# stm32_ros_car.net
KiCad netlist of a schematic drawn in Altium Designer
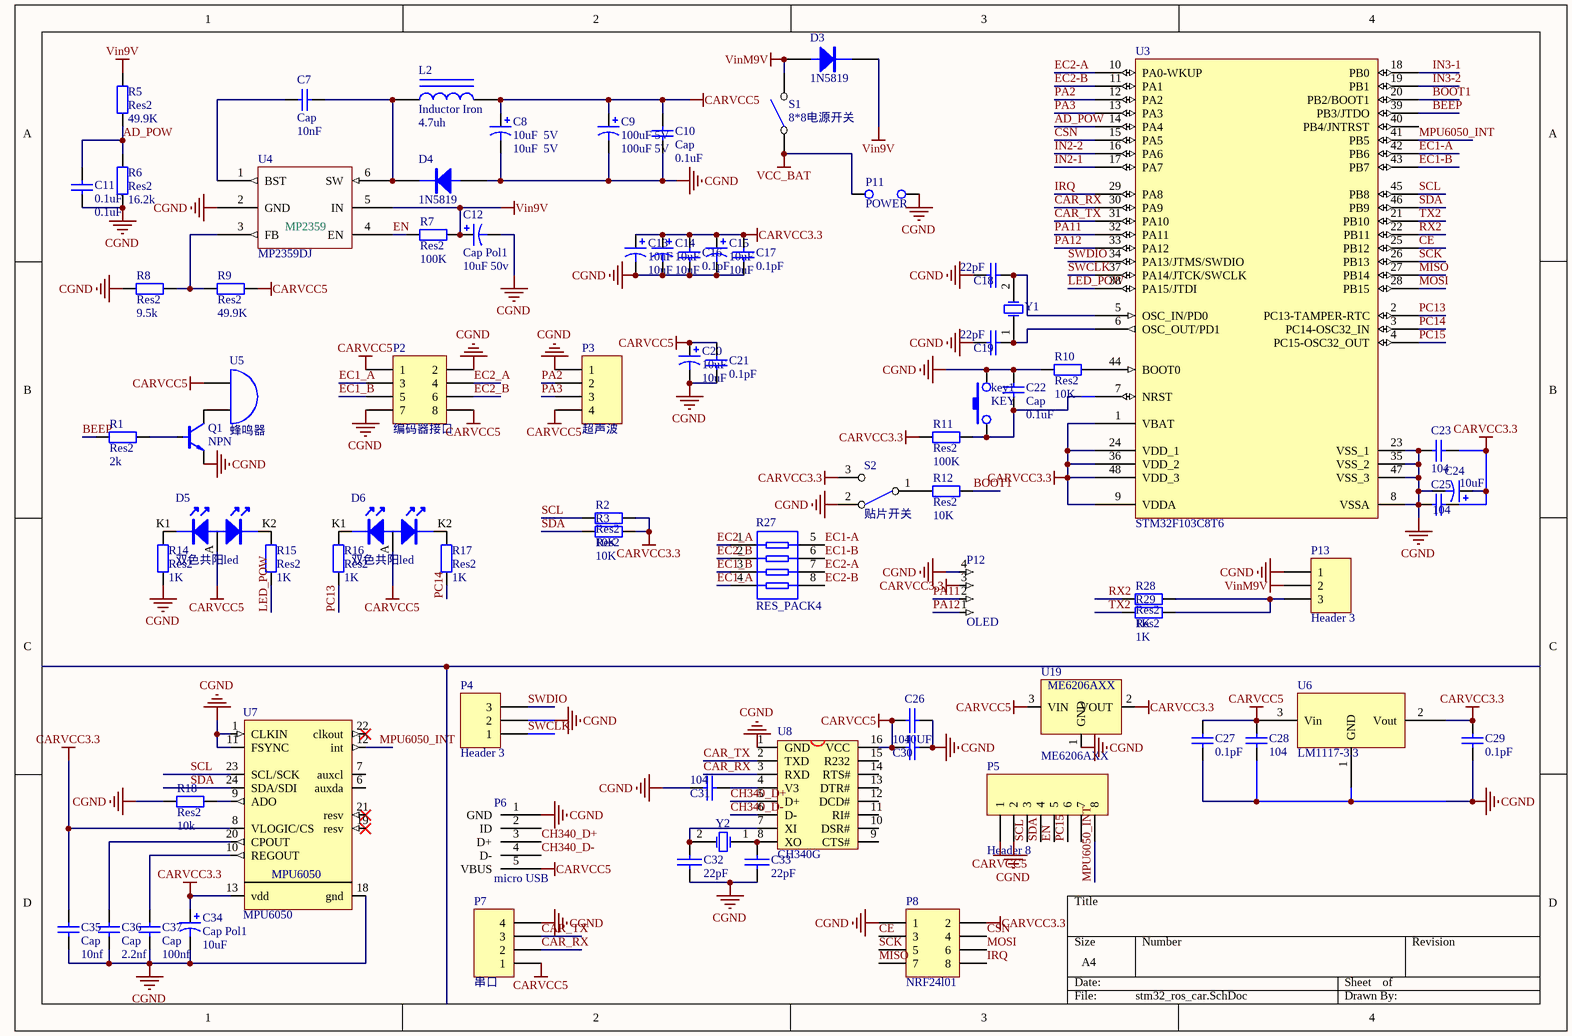
[diagram p0: stm32_ros_car.SchDoc]

(export (version "E")
  (design (tool "Eeschema 10.0.6"))
  (components
    (comp (ref "C7")
      (value "Cap")
      (footprint "LC-0603_C")
      (description "Capacitor")
      (fields (field (name "ALTIUM_VALUE") "10nF") (field (name "PUBLISHER") "Altium Limited"))
      (libsource (lib "Miscellaneous Devices") (part "Cap"))
    )
    (comp (ref "C8")
      (value "10uF  5V")
      (footprint "LC-1210_C")
      (description "Polarized Capacitor (Radial)")
      (fields (field (name "ALTIUM_VALUE") "10uF  5V") (field (name "PUBLISHER") "Altium Limited"))
      (libsource (lib "Miscellaneous Devices") (part "Cap Pol1"))
    )
    (comp (ref "C9")
      (value "100uF 5V")
      (footprint "电容HONOR_63X77")
      (description "Polarized Capacitor (Radial)")
      (fields (field (name "ALTIUM_VALUE") "100uF 5V") (field (name "PUBLISHER") "Altium Limited"))
      (libsource (lib "Miscellaneous Devices") (part "Cap Pol1"))
    )
    (comp (ref "C10")
      (value "Cap")
      (footprint "LC-0603_C")
      (description "Capacitor")
      (fields (field (name "ALTIUM_VALUE") "0.1uF") (field (name "PUBLISHER") "Altium Limited"))
      (libsource (lib "Miscellaneous Devices") (part "Cap"))
    )
    (comp (ref "C11")
      (value "0.1uF")
      (footprint "LC-0603_C")
      (description "Capacitor")
      (fields (field (name "ALTIUM_VALUE") "0.1uF") (field (name "PUBLISHER") "Altium Limited"))
      (libsource (lib "Miscellaneous Devices") (part "Cap"))
    )
    (comp (ref "C12")
      (value "Cap Pol1")
      (footprint "电容HONOR_63X54")
      (description "Polarized Capacitor (Radial)")
      (fields (field (name "ALTIUM_VALUE") "10uF 50v") (field (name "PUBLISHER") "Altium Limited"))
      (libsource (lib "Miscellaneous Devices") (part "Cap Pol1"))
    )
    (comp (ref "C13")
      (value "10uF")
      (footprint "电容HONOR_63X77")
      (description "Polarized Capacitor (Radial)")
      (fields (field (name "ALTIUM_VALUE") "10uF") (field (name "PUBLISHER") "Altium Limited"))
      (libsource (lib "Miscellaneous Devices") (part "Cap Pol1"))
    )
    (comp (ref "C14")
      (value "10uF")
      (footprint "LC-1210_C")
      (description "Polarized Capacitor (Radial)")
      (fields (field (name "ALTIUM_VALUE") "10uF") (field (name "PUBLISHER") "Altium Limited"))
      (libsource (lib "Miscellaneous Devices") (part "Cap Pol1"))
    )
    (comp (ref "C15")
      (value "10uF")
      (footprint "LC-1210_C")
      (description "Polarized Capacitor (Radial)")
      (fields (field (name "ALTIUM_VALUE") "10uF") (field (name "PUBLISHER") "Altium Limited"))
      (libsource (lib "Miscellaneous Devices") (part "Cap Pol1"))
    )
    (comp (ref "C16")
      (value "0.1pF")
      (footprint "LC-0603_C")
      (description "Capacitor")
      (fields (field (name "Comment") "Cap") (field (name "PUBLISHER") "Altium Limited"))
      (libsource (lib "Miscellaneous Devices") (part "Cap"))
    )
    (comp (ref "C17")
      (value "0.1pF")
      (footprint "LC-0603_C")
      (description "Capacitor")
      (fields (field (name "Comment") "Cap") (field (name "PUBLISHER") "Altium Limited"))
      (libsource (lib "Miscellaneous Devices") (part "Cap"))
    )
    (comp (ref "C18")
      (value "22pF")
      (footprint "LC-0603_C")
      (fields (field (name "Comment") "CAP"))
      (libsource (lib "MySchLib") (part "CAP"))
    )
    (comp (ref "C19")
      (value "22pF")
      (footprint "LC-0603_C")
      (fields (field (name "Comment") "CAP"))
      (libsource (lib "MySchLib") (part "CAP"))
    )
    (comp (ref "C20")
      (value "10uF")
      (footprint "LC-1210_C")
      (description "Polarized Capacitor (Radial)")
      (fields (field (name "ALTIUM_VALUE") "10uF") (field (name "PUBLISHER") "Altium Limited"))
      (libsource (lib "Miscellaneous Devices") (part "Cap Pol1"))
    )
    (comp (ref "C21")
      (value "0.1pF")
      (footprint "LC-0603_C")
      (description "Capacitor")
      (fields (field (name "Comment") "Cap") (field (name "PUBLISHER") "Altium Limited"))
      (libsource (lib "Miscellaneous Devices") (part "Cap"))
    )
    (comp (ref "C22")
      (value "Cap")
      (footprint "LC-0603_C")
      (description "Capacitor")
      (fields (field (name "ALTIUM_VALUE") "0.1uF") (field (name "PUBLISHER") "Altium Limited"))
      (libsource (lib "Miscellaneous Devices") (part "Cap"))
    )
    (comp (ref "C23")
      (value "104")
      (footprint "LC-0603_C")
      (description "Capacitor")
      (fields (field (name "Comment") "Cap") (field (name "PUBLISHER") "Altium Limited"))
      (libsource (lib "Miscellaneous Devices") (part "Cap"))
    )
    (comp (ref "C24")
      (value "10uF")
      (footprint "LC-1210_C")
      (description "Polarized Capacitor (Radial)")
      (fields (field (name "PUBLISHER") "Altium Limited"))
      (libsource (lib "Miscellaneous Devices") (part "Cap Pol1"))
    )
    (comp (ref "C25")
      (value "104")
      (footprint "LC-0603_C")
      (description "Capacitor")
      (fields (field (name "Comment") "Cap") (field (name "PUBLISHER") "Altium Limited"))
      (libsource (lib "Miscellaneous Devices") (part "Cap"))
    )
    (comp (ref "C26")
      (value "10UF")
      (footprint "LC-0603_C")
      (fields (field (name "Comment") "CAP"))
      (libsource (lib "MySchLib") (part "CAP"))
    )
    (comp (ref "C27")
      (value "0.1pF")
      (footprint "LC-0603_C")
      (description "Capacitor")
      (fields (field (name "Comment") "Cap") (field (name "PUBLISHER") "Altium Limited"))
      (libsource (lib "Miscellaneous Devices") (part "Cap"))
    )
    (comp (ref "C28")
      (value "104")
      (footprint "LC-Standard-FootPrints-AD-V1.00:LC-1210_C")
      (description "Capacitor")
      (fields (field (name "Comment") "Cap") (field (name "PUBLISHER") "Altium Limited"))
      (libsource (lib "Miscellaneous Devices") (part "Cap"))
    )
    (comp (ref "C29")
      (value "0.1pF")
      (footprint "LC-0603_C")
      (description "Capacitor")
      (fields (field (name "Comment") "Cap") (field (name "PUBLISHER") "Altium Limited"))
      (libsource (lib "Miscellaneous Devices") (part "Cap"))
    )
    (comp (ref "C30")
      (value "104")
      (footprint "LC-1206_C")
      (fields (field (name "Comment") "CAP"))
      (libsource (lib "MySchLib") (part "CAP"))
    )
    (comp (ref "C31")
      (value "104")
      (footprint "LC-0603_C")
      (fields (field (name "Comment") "CAP"))
      (libsource (lib "MySchLib") (part "CAP"))
    )
    (comp (ref "C32")
      (value "22pF")
      (footprint "LC-0603_C")
      (fields (field (name "Comment") "CAP"))
      (libsource (lib "MySchLib") (part "CAP"))
    )
    (comp (ref "C33")
      (value "22pF")
      (footprint "LC-0603_C")
      (fields (field (name "Comment") "CAP"))
      (libsource (lib "MySchLib") (part "CAP"))
    )
    (comp (ref "C34")
      (value "Cap Pol1")
      (footprint "LC-1210_C")
      (description "Polarized Capacitor (Radial)")
      (fields (field (name "ALTIUM_VALUE") "10uF") (field (name "PUBLISHER") "Altium Limited"))
      (libsource (lib "Miscellaneous Devices") (part "Cap Pol1"))
    )
    (comp (ref "C35")
      (value "Cap")
      (footprint "LC-0603_C")
      (description "Capacitor")
      (fields (field (name "ALTIUM_VALUE") "10nf") (field (name "PUBLISHER") "Altium Limited"))
      (libsource (lib "Miscellaneous Devices") (part "Cap"))
    )
    (comp (ref "C36")
      (value "Cap")
      (footprint "LC-0603_C")
      (description "Capacitor")
      (fields (field (name "ALTIUM_VALUE") "2.2nf") (field (name "PUBLISHER") "Altium Limited"))
      (libsource (lib "Miscellaneous Devices") (part "Cap"))
    )
    (comp (ref "C37")
      (value "Cap")
      (footprint "LC-0603_C")
      (description "Capacitor")
      (fields (field (name "ALTIUM_VALUE") "100nf") (field (name "PUBLISHER") "Altium Limited"))
      (libsource (lib "Miscellaneous Devices") (part "Cap"))
    )
    (comp (ref "D3") (value "1N5819") (footprint "SMA") (libsource (lib "ARAMYLIB") (part "1N4001")))
    (comp (ref "D4") (value "1N5819") (footprint "SMA") (libsource (lib "ARAMYLIB") (part "1N4001")))
    (comp (ref "D5") (value "双色共阳led") (footprint "共阳双色LED") (libsource (lib "ROS_CAR_LIB") (part "双色共阳led")))
    (comp (ref "D6") (value "双色共阳led") (footprint "共阳双色LED") (libsource (lib "ROS_CAR_LIB") (part "双色共阳led")))
    (comp (ref "key1") (value "KEY") (footprint "SMD轻触按键") (libsource (lib "ROS_CAR_LIB") (part "KEY")))
    (comp (ref "L2")
      (value "Inductor Iron")
      (footprint "电感GDCD4532")
      (description "Magnetic-Core Inductor")
      (fields (field (name "ALTIUM_VALUE") "4.7uh") (field (name "PUBLISHER") "Altium Limited"))
      (libsource (lib "Miscellaneous Devices") (part "Inductor Iron"))
    )
    (comp (ref "P2")
      (value "编码器接口")
      (footprint "HDR2X4")
      (description "Header, 4-Pin, Dual row")
      (fields (field (name "PUBLISHER") "Altium Limited"))
      (libsource (lib "Miscellaneous Connectors") (part "Header 4X2"))
    )
    (comp (ref "P3")
      (value "超声波")
      (footprint "HDR1X4")
      (description "Header, 4-Pin")
      (fields (field (name "PUBLISHER") "Altium Limited"))
      (libsource (lib "Miscellaneous Connectors") (part "Header 4"))
    )
    (comp (ref "P4")
      (value "Header 3")
      (footprint "HDR1X3")
      (description "Header, 3-Pin")
      (fields (field (name "PUBLISHER") "Altium Limited"))
      (libsource (lib "Miscellaneous Connectors") (part "Header 3"))
    )
    (comp (ref "P5")
      (value "Header 8")
      (footprint "HDR1X8")
      (description "Header, 8-Pin")
      (fields (field (name "PUBLISHER") "Altium Limited"))
      (libsource (lib "Miscellaneous Connectors") (part "Header 8"))
    )
    (comp (ref "P6")
      (value "micro USB")
      (footprint "micro 5P沉板式0.8四脚全插无导位有孔")
      (libsource (lib "ROS_CAR_LIB") (part "micro 5P"))
    )
    (comp (ref "P7")
      (value "串口")
      (footprint "HDR1X4")
      (description "Header, 4-Pin")
      (fields (field (name "PUBLISHER") "Altium Limited"))
      (libsource (lib "") (part "Header 4_1"))
    )
    (comp (ref "P8")
      (value "NRF24l01")
      (footprint "HDR2X4")
      (description "Header, 4-Pin, Dual row")
      (fields (field (name "PUBLISHER") "Altium Limited"))
      (libsource (lib "Miscellaneous Connectors") (part "Header 4X2"))
    )
    (comp (ref "P11") (value "POWER") (footprint "电源") (libsource (lib "ROS_CAR_LIB") (part "POWER")))
    (comp (ref "P12")
      (value "OLED")
      (footprint "1.0MM 翻盖 下接 FPC连接器 4P")
      (libsource (lib "ros_car_lib") (part "FPC 4P 1MM"))
    )
    (comp (ref "P13")
      (value "Header 3")
      (footprint "AMP 3针连接件")
      (description "Header, 3-Pin")
      (fields (field (name "PUBLISHER") "Altium Limited"))
      (libsource (lib "") (part "Header 3_1"))
    )
    (comp (ref "Q1") (value "NPN") (footprint "LC-SOT-23") (libsource (lib "ARAMYLIB") (part "NPN")))
    (comp (ref "R1")
      (value "Res2")
      (footprint "LC-0603_R")
      (description "Resistor")
      (fields (field (name "ALTIUM_VALUE") "2k") (field (name "PUBLISHER") "Altium Limited"))
      (libsource (lib "") (part "Res2_2"))
    )
    (comp (ref "R2")
      (value "Res2")
      (footprint "LC-0603_R")
      (description "Resistor")
      (fields (field (name "ALTIUM_VALUE") "10K") (field (name "PUBLISHER") "Altium Limited"))
      (libsource (lib "") (part "Res2_2"))
    )
    (comp (ref "R3")
      (value "Res2")
      (footprint "LC-0603_R")
      (description "Resistor")
      (fields (field (name "ALTIUM_VALUE") "10K") (field (name "PUBLISHER") "Altium Limited"))
      (libsource (lib "") (part "Res2_2"))
    )
    (comp (ref "R5")
      (value "Res2")
      (footprint "LC-0603_R")
      (description "Resistor")
      (fields (field (name "ALTIUM_VALUE") "49.9K") (field (name "PUBLISHER") "Altium Limited"))
      (libsource (lib "") (part "Res2_3"))
    )
    (comp (ref "R6")
      (value "Res2")
      (footprint "LC-0603_R")
      (description "Resistor")
      (fields (field (name "ALTIUM_VALUE") "16.2k") (field (name "PUBLISHER") "Altium Limited"))
      (libsource (lib "") (part "Res2_3"))
    )
    (comp (ref "R7")
      (value "Res2")
      (footprint "LC-0603_R")
      (description "Resistor")
      (fields (field (name "ALTIUM_VALUE") "100K") (field (name "PUBLISHER") "Altium Limited"))
      (libsource (lib "Miscellaneous Devices") (part "Res2"))
    )
    (comp (ref "R8")
      (value "Res2")
      (footprint "LC-0603_R")
      (description "Resistor")
      (fields (field (name "ALTIUM_VALUE") "9.5k") (field (name "PUBLISHER") "Altium Limited"))
      (libsource (lib "") (part "Res2_2"))
    )
    (comp (ref "R9")
      (value "Res2")
      (footprint "LC-0603_R")
      (description "Resistor")
      (fields (field (name "ALTIUM_VALUE") "49.9K") (field (name "PUBLISHER") "Altium Limited"))
      (libsource (lib "") (part "Res2_2"))
    )
    (comp (ref "R10")
      (value "Res2")
      (footprint "LC-0603_R")
      (description "Resistor")
      (fields (field (name "ALTIUM_VALUE") "10K") (field (name "PUBLISHER") "Altium Limited"))
      (libsource (lib "Miscellaneous Devices") (part "Res2"))
    )
    (comp (ref "R11")
      (value "Res2")
      (footprint "LC-0603_R")
      (description "Resistor")
      (fields (field (name "ALTIUM_VALUE") "100K") (field (name "PUBLISHER") "Altium Limited"))
      (libsource (lib "Miscellaneous Devices") (part "Res2"))
    )
    (comp (ref "R12")
      (value "Res2")
      (footprint "LC-0603_R")
      (description "Resistor")
      (fields (field (name "ALTIUM_VALUE") "10K") (field (name "PUBLISHER") "Altium Limited"))
      (libsource (lib "") (part "Res2_2"))
    )
    (comp (ref "R14")
      (value "Res2")
      (footprint "LC-0603_R")
      (description "Resistor")
      (fields (field (name "ALTIUM_VALUE") "1K") (field (name "PUBLISHER") "Altium Limited"))
      (libsource (lib "") (part "Res2_1"))
    )
    (comp (ref "R15")
      (value "Res2")
      (footprint "LC-0603_R")
      (description "Resistor")
      (fields (field (name "ALTIUM_VALUE") "1K") (field (name "PUBLISHER") "Altium Limited"))
      (libsource (lib "") (part "Res2_1"))
    )
    (comp (ref "R16")
      (value "Res2")
      (footprint "LC-0603_R")
      (description "Resistor")
      (fields (field (name "ALTIUM_VALUE") "1K") (field (name "PUBLISHER") "Altium Limited"))
      (libsource (lib "") (part "Res2_1"))
    )
    (comp (ref "R17")
      (value "Res2")
      (footprint "LC-0603_R")
      (description "Resistor")
      (fields (field (name "ALTIUM_VALUE") "1K") (field (name "PUBLISHER") "Altium Limited"))
      (libsource (lib "") (part "Res2_1"))
    )
    (comp (ref "R18")
      (value "Res2")
      (footprint "LC-0603_R")
      (description "Resistor")
      (fields (field (name "ALTIUM_VALUE") "10k") (field (name "PUBLISHER") "Altium Limited"))
      (libsource (lib "") (part "Res2_2"))
    )
    (comp (ref "R27") (value "RES_PACK4") (footprint "RES4") (libsource (lib "ARAMYLIB") (part "RES_PACK4")))
    (comp (ref "R28")
      (value "Res2")
      (footprint "LC-0603_R")
      (description "Resistor")
      (fields (field (name "ALTIUM_VALUE") "1K") (field (name "PUBLISHER") "Altium Limited"))
      (libsource (lib "Miscellaneous Devices") (part "Res2"))
    )
    (comp (ref "R29")
      (value "Res2")
      (footprint "LC-0603_R")
      (description "Resistor")
      (fields (field (name "ALTIUM_VALUE") "1K") (field (name "PUBLISHER") "Altium Limited"))
      (libsource (lib "Miscellaneous Devices") (part "Res2"))
    )
    (comp (ref "S1") (value "8*8电源开关") (footprint "8*8自锁开关") (libsource (lib "ROS_CAR_LIB") (part "8*8电源开关")))
    (comp (ref "S2") (value "贴片开关") (footprint "KEY") (libsource (lib "aramy_四轴") (part "贴片开关")))
    (comp (ref "U3")
      (value "STM32F103C8T6")
      (footprint "LQFP48_L")
      (description "STM32 ARM-based 32-bit MCU with 64 Kbytes Flash, 48-pin LQFP, Industrial Temperature")
      (fields (field (name "PUBLISHER") "Altium Limited"))
      (libsource (lib "ST Microcontroller 32-Bit STM32") (part "STM32F103C8T6"))
    )
    (comp (ref "U4")
      (value "MP2359DJ")
      (footprint "LC-SOT-23-6")
      (libsource (lib "ARAMYLIB") (part "MP2359DJ"))
    )
    (comp (ref "U5")
      (value "蜂鸣器")
      (footprint "BELL")
      (description "Bell")
      (libsource (lib "ARAMYLIB") (part "蜂鸣器"))
    )
    (comp (ref "U6")
      (value "LM1117-3.3")
      (footprint "SOT223")
      (libsource (lib "MySchLib") (part "LM1117-3.3"))
    )
    (comp (ref "U7") (value "MPU6050") (footprint "QFN24") (libsource (lib "aramy_四轴") (part "MPU6050")))
    (comp (ref "U8")
      (value "CH340G")
      (footprint "SOP16M")
      (description "USB2UART")
      (libsource (lib "EliteSTM32封装库") (part "CH340G"))
    )
    (comp (ref "U19")
      (value "ME6206AXX")
      (footprint "LC-SOT-89")
      (libsource (lib "ARAMY_四轴") (part "ME6206AXX"))
    )
    (comp (ref "Y1")
      (value "12MHz")
      (footprint "49SMD")
      (description "Crystal Oscillator")
      (fields (field (name "PUBLISHER") "Altium Limited"))
      (libsource (lib "ALIENTEK_底板封装库") (part "XTAL"))
    )
    (comp (ref "Y2")
      (value "12MHz")
      (footprint "49SMD")
      (description "Crystal Oscillator")
      (fields (field (name "PUBLISHER") "Altium Limited"))
      (libsource (lib "ALIENTEK_底板封装库") (part "XTAL"))
    )
  )
  (nets
    (net (code "1") (name "/AD_POW") (class "Default")
      (node (ref "C11") (pin "1") (pinfunction "1_1") (pintype "passive"))
      (node (ref "R5") (pin "2") (pinfunction "2_2") (pintype "passive"))
      (node (ref "R6") (pin "1") (pinfunction "1_1") (pintype "passive"))
      (node (ref "U3") (pin "14") (pinfunction "PA4_14") (pintype "bidirectional"))
    )
    (net (code "2") (name "/BEEP") (class "Default")
      (node (ref "R1") (pin "2") (pinfunction "2_2") (pintype "passive"))
      (node (ref "U3") (pin "39") (pinfunction "PB3/JTDO_39") (pintype "bidirectional"))
    )
    (net (code "3") (name "/BOOT1") (class "Default")
      (node (ref "R12") (pin "1") (pinfunction "1_1") (pintype "passive"))
      (node (ref "U3") (pin "20") (pinfunction "PB2/BOOT1_20") (pintype "bidirectional"))
    )
    (net (code "4") (name "/CAR_RX") (class "Default")
      (node (ref "P7") (pin "2") (pinfunction "2_2") (pintype "passive"))
      (node (ref "U3") (pin "30") (pinfunction "PA9_30") (pintype "bidirectional"))
      (node (ref "U8") (pin "3") (pinfunction "RXD_3") (pintype "passive"))
    )
    (net (code "5") (name "/CAR_TX") (class "Default")
      (node (ref "P7") (pin "3") (pinfunction "3_3") (pintype "passive"))
      (node (ref "U3") (pin "31") (pinfunction "PA10_31") (pintype "bidirectional"))
      (node (ref "U8") (pin "2") (pinfunction "TXD_2") (pintype "passive"))
    )
    (net (code "6") (name "/CE") (class "Default")
      (node (ref "P8") (pin "3") (pinfunction "3_3") (pintype "passive"))
      (node (ref "U3") (pin "25") (pinfunction "PB12_25") (pintype "bidirectional"))
    )
    (net (code "7") (name "/CH340_D+") (class "Default")
      (node (ref "P6") (pin "3") (pinfunction "D+_3") (pintype "passive"))
      (node (ref "U8") (pin "5") (pinfunction "D+_5") (pintype "passive"))
    )
    (net (code "8") (name "/CH340_D-") (class "Default")
      (node (ref "P6") (pin "4") (pinfunction "D-_4") (pintype "passive"))
      (node (ref "U8") (pin "6") (pinfunction "D-_6") (pintype "passive"))
    )
    (net (code "9") (name "/CSN") (class "Default")
      (node (ref "P8") (pin "4") (pinfunction "4_4") (pintype "passive"))
      (node (ref "U3") (pin "15") (pinfunction "PA5_15") (pintype "bidirectional"))
    )
    (net (code "10") (name "/EC1-A") (class "Default")
      (node (ref "R27") (pin "5") (pinfunction "5_5") (pintype "passive"))
      (node (ref "U3") (pin "42") (pinfunction "PB6_42") (pintype "bidirectional"))
    )
    (net (code "11") (name "/EC1-B") (class "Default")
      (node (ref "R27") (pin "6") (pinfunction "6_6") (pintype "passive"))
      (node (ref "U3") (pin "43") (pinfunction "PB7_43") (pintype "bidirectional"))
    )
    (net (code "12") (name "/EC1_A") (class "Default")
      (node (ref "P2") (pin "3") (pinfunction "3_3") (pintype "passive"))
      (node (ref "R27") (pin "4") (pinfunction "4_4") (pintype "passive"))
    )
    (net (code "13") (name "/EC1_B") (class "Default")
      (node (ref "P2") (pin "5") (pinfunction "5_5") (pintype "passive"))
      (node (ref "R27") (pin "3") (pinfunction "3_3") (pintype "passive"))
    )
    (net (code "14") (name "/EC2-A") (class "Default")
      (node (ref "R27") (pin "7") (pinfunction "7_7") (pintype "passive"))
      (node (ref "U3") (pin "10") (pinfunction "PA0-WKUP_10") (pintype "bidirectional"))
    )
    (net (code "15") (name "/EC2-B") (class "Default")
      (node (ref "R27") (pin "8") (pinfunction "8_8") (pintype "passive"))
      (node (ref "U3") (pin "11") (pinfunction "PA1_11") (pintype "bidirectional"))
    )
    (net (code "16") (name "/EC2_A") (class "Default")
      (node (ref "P2") (pin "4") (pinfunction "4_4") (pintype "passive"))
      (node (ref "R27") (pin "1") (pinfunction "1_1") (pintype "passive"))
    )
    (net (code "17") (name "/EC2_B") (class "Default")
      (node (ref "P2") (pin "6") (pinfunction "6_6") (pintype "passive"))
      (node (ref "R27") (pin "2") (pinfunction "2_2") (pintype "passive"))
    )
    (net (code "18") (name "/EN") (class "Default")
      (node (ref "P5") (pin "5") (pinfunction "5_5") (pintype "passive"))
      (node (ref "R7") (pin "1") (pinfunction "1_1") (pintype "passive"))
      (node (ref "U4") (pin "4") (pinfunction "EN_4") (pintype "power_in"))
    )
    (net (code "19") (name "/IN2-1") (class "Default")
      (node (ref "U3") (pin "17") (pinfunction "PA7_17") (pintype "bidirectional"))
    )
    (net (code "20") (name "/IN2-2") (class "Default")
      (node (ref "U3") (pin "16") (pinfunction "PA6_16") (pintype "bidirectional"))
    )
    (net (code "21") (name "/IN3-1") (class "Default")
      (node (ref "U3") (pin "18") (pinfunction "PB0_18") (pintype "bidirectional"))
    )
    (net (code "22") (name "/IN3-2") (class "Default")
      (node (ref "U3") (pin "19") (pinfunction "PB1_19") (pintype "bidirectional"))
    )
    (net (code "23") (name "/IRQ") (class "Default")
      (node (ref "P8") (pin "8") (pinfunction "8_8") (pintype "passive"))
      (node (ref "U3") (pin "29") (pinfunction "PA8_29") (pintype "bidirectional"))
    )
    (net (code "24") (name "/LED_POW") (class "Default")
      (node (ref "R15") (pin "1") (pinfunction "1_1") (pintype "passive"))
      (node (ref "U3") (pin "38") (pinfunction "PA15/JTDI_38") (pintype "bidirectional"))
    )
    (net (code "25") (name "/MISO") (class "Default")
      (node (ref "P8") (pin "7") (pinfunction "7_7") (pintype "passive"))
      (node (ref "U3") (pin "27") (pinfunction "PB14_27") (pintype "bidirectional"))
    )
    (net (code "26") (name "/MOSI") (class "Default")
      (node (ref "P8") (pin "6") (pinfunction "6_6") (pintype "passive"))
      (node (ref "U3") (pin "28") (pinfunction "PB15_28") (pintype "bidirectional"))
    )
    (net (code "27") (name "/MPU6050_INT") (class "Default")
      (node (ref "P5") (pin "8") (pinfunction "8_8") (pintype "passive"))
      (node (ref "U3") (pin "41") (pinfunction "PB5_41") (pintype "bidirectional"))
      (node (ref "U7") (pin "12") (pinfunction "int_12") (pintype "output"))
    )
    (net (code "28") (name "/PA2") (class "Default")
      (node (ref "P3") (pin "2") (pinfunction "2_2") (pintype "passive"))
      (node (ref "U3") (pin "12") (pinfunction "PA2_12") (pintype "bidirectional"))
    )
    (net (code "29") (name "/PA3") (class "Default")
      (node (ref "P3") (pin "3") (pinfunction "3_3") (pintype "passive"))
      (node (ref "U3") (pin "13") (pinfunction "PA3_13") (pintype "bidirectional"))
    )
    (net (code "30") (name "/PA11") (class "Default")
      (node (ref "P12") (pin "2") (pinfunction "2_2") (pintype "input"))
      (node (ref "U3") (pin "32") (pinfunction "PA11_32") (pintype "bidirectional"))
    )
    (net (code "31") (name "/PA12") (class "Default")
      (node (ref "P12") (pin "1") (pinfunction "1_1") (pintype "input"))
      (node (ref "U3") (pin "33") (pinfunction "PA12_33") (pintype "bidirectional"))
    )
    (net (code "32") (name "/PC13") (class "Default")
      (node (ref "R16") (pin "1") (pinfunction "1_1") (pintype "passive"))
      (node (ref "U3") (pin "2") (pinfunction "PC13-TAMPER-RTC_2") (pintype "bidirectional"))
    )
    (net (code "33") (name "/PC14") (class "Default")
      (node (ref "R17") (pin "1") (pinfunction "1_1") (pintype "passive"))
      (node (ref "U3") (pin "3") (pinfunction "PC14-OSC32_IN_3") (pintype "bidirectional"))
    )
    (net (code "34") (name "/PC15") (class "Default")
      (node (ref "P5") (pin "6") (pinfunction "6_6") (pintype "passive"))
      (node (ref "U3") (pin "4") (pinfunction "PC15-OSC32_OUT_4") (pintype "bidirectional"))
    )
    (net (code "35") (name "/RX2") (class "Default")
      (node (ref "R28") (pin "1") (pinfunction "1_1") (pintype "passive"))
      (node (ref "U3") (pin "22") (pinfunction "PB11_22") (pintype "bidirectional"))
    )
    (net (code "36") (name "/SCK") (class "Default")
      (node (ref "P8") (pin "5") (pinfunction "5_5") (pintype "passive"))
      (node (ref "U3") (pin "26") (pinfunction "PB13_26") (pintype "bidirectional"))
    )
    (net (code "37") (name "/SCL") (class "Default")
      (node (ref "P5") (pin "3") (pinfunction "3_3") (pintype "passive"))
      (node (ref "R2") (pin "2") (pinfunction "2_2") (pintype "passive"))
      (node (ref "U3") (pin "45") (pinfunction "PB8_45") (pintype "bidirectional"))
      (node (ref "U7") (pin "23") (pinfunction "SCL/SCK_23") (pintype "bidirectional"))
    )
    (net (code "38") (name "/SDA") (class "Default")
      (node (ref "P5") (pin "4") (pinfunction "4_4") (pintype "passive"))
      (node (ref "R3") (pin "2") (pinfunction "2_2") (pintype "passive"))
      (node (ref "U3") (pin "46") (pinfunction "PB9_46") (pintype "bidirectional"))
      (node (ref "U7") (pin "24") (pinfunction "SDA/SDI_24") (pintype "bidirectional"))
    )
    (net (code "39") (name "/SWCLK") (class "Default")
      (node (ref "P4") (pin "1") (pinfunction "1_1") (pintype "passive"))
      (node (ref "U3") (pin "37") (pinfunction "PA14/JTCK/SWCLK_37") (pintype "bidirectional"))
    )
    (net (code "40") (name "/SWDIO") (class "Default")
      (node (ref "P4") (pin "3") (pinfunction "3_3") (pintype "passive"))
      (node (ref "U3") (pin "34") (pinfunction "PA13/JTMS/SWDIO_34") (pintype "bidirectional"))
    )
    (net (code "41") (name "/TX2") (class "Default")
      (node (ref "R29") (pin "1") (pinfunction "1_1") (pintype "passive"))
      (node (ref "U3") (pin "21") (pinfunction "PB10_21") (pintype "bidirectional"))
    )
    (net (code "42") (name "CARVCC3.3") (class "Default")
      (node (ref "C13") (pin "1") (pinfunction "1_1") (pintype "passive"))
      (node (ref "C14") (pin "1") (pinfunction "1_1") (pintype "passive"))
      (node (ref "C15") (pin "1") (pinfunction "1_1") (pintype "passive"))
      (node (ref "C16") (pin "1") (pinfunction "1_1") (pintype "passive"))
      (node (ref "C17") (pin "1") (pinfunction "1_1") (pintype "passive"))
      (node (ref "C23") (pin "1") (pinfunction "1_1") (pintype "passive"))
      (node (ref "C24") (pin "1") (pinfunction "1_1") (pintype "passive"))
      (node (ref "C25") (pin "1") (pinfunction "1_1") (pintype "passive"))
      (node (ref "C29") (pin "1") (pinfunction "1_1") (pintype "passive"))
      (node (ref "C34") (pin "1") (pinfunction "1_1") (pintype "passive"))
      (node (ref "C35") (pin "2") (pinfunction "2_2") (pintype "passive"))
      (node (ref "P12") (pin "3") (pinfunction "3_3") (pintype "input"))
      (node (ref "P8") (pin "2") (pinfunction "2_2") (pintype "passive"))
      (node (ref "R11") (pin "1") (pinfunction "1_1") (pintype "passive"))
      (node (ref "R2") (pin "1") (pinfunction "1_1") (pintype "passive"))
      (node (ref "R3") (pin "1") (pinfunction "1_1") (pintype "passive"))
      (node (ref "S2") (pin "3") (pinfunction "NO1_3") (pintype "passive"))
      (node (ref "U19") (pin "2") (pinfunction "VOUT_2") (pintype "passive"))
      (node (ref "U3") (pin "1") (pinfunction "VBAT_1") (pintype "power_in"))
      (node (ref "U3") (pin "24") (pinfunction "VDD_1_24") (pintype "power_in"))
      (node (ref "U3") (pin "36") (pinfunction "VDD_2_36") (pintype "power_in"))
      (node (ref "U3") (pin "48") (pinfunction "VDD_3_48") (pintype "power_in"))
      (node (ref "U3") (pin "9") (pinfunction "VDDA_9") (pintype "power_in"))
      (node (ref "U6") (pin "2") (pinfunction "Vout_2") (pintype "passive"))
      (node (ref "U7") (pin "13") (pinfunction "vdd_13") (pintype "power_in"))
      (node (ref "U7") (pin "8") (pinfunction "VLOGIC/CS_8") (pintype "bidirectional"))
    )
    (net (code "43") (name "CARVCC5") (class "Default")
      (node (ref "C10") (pin "2") (pinfunction "2_2") (pintype "passive"))
      (node (ref "C20") (pin "1") (pinfunction "1_1") (pintype "passive"))
      (node (ref "C21") (pin "1") (pinfunction "1_1") (pintype "passive"))
      (node (ref "C26") (pin "2") (pinfunction "2_2") (pintype "passive"))
      (node (ref "C27") (pin "1") (pinfunction "1_1") (pintype "passive"))
      (node (ref "C28") (pin "2") (pinfunction "2_2") (pintype "passive"))
      (node (ref "C30") (pin "1") (pinfunction "1_1") (pintype "passive"))
      (node (ref "C8") (pin "1") (pinfunction "1_1") (pintype "passive"))
      (node (ref "C9") (pin "1") (pinfunction "1_1") (pintype "passive"))
      (node (ref "D5") (pin "A") (pinfunction "2_A") (pintype "passive"))
      (node (ref "D6") (pin "A") (pinfunction "2_A") (pintype "passive"))
      (node (ref "L2") (pin "2") (pinfunction "2_2") (pintype "passive"))
      (node (ref "P2") (pin "1") (pinfunction "1_1") (pintype "passive"))
      (node (ref "P2") (pin "8") (pinfunction "8_8") (pintype "passive"))
      (node (ref "P3") (pin "4") (pinfunction "4_4") (pintype "passive"))
      (node (ref "P5") (pin "1") (pinfunction "1_1") (pintype "passive"))
      (node (ref "P6") (pin "5") (pinfunction "VBUS_5") (pintype "passive"))
      (node (ref "P7") (pin "1") (pinfunction "1_1") (pintype "passive"))
      (node (ref "R9") (pin "1") (pinfunction "1_1") (pintype "passive"))
      (node (ref "U19") (pin "3") (pinfunction "VIN_3") (pintype "power_in"))
      (node (ref "U5") (pin "1") (pinfunction "A_1") (pintype "passive"))
      (node (ref "U6") (pin "3") (pinfunction "Vin_3") (pintype "passive"))
      (node (ref "U8") (pin "16") (pinfunction "VCC_16") (pintype "passive"))
    )
    (net (code "44") (name "CGND") (class "Default")
      (node (ref "C10") (pin "1") (pinfunction "1_1") (pintype "passive"))
      (node (ref "C11") (pin "2") (pinfunction "2_2") (pintype "passive"))
      (node (ref "C12") (pin "2") (pinfunction "2_2") (pintype "passive"))
      (node (ref "C13") (pin "2") (pinfunction "2_2") (pintype "passive"))
      (node (ref "C14") (pin "2") (pinfunction "2_2") (pintype "passive"))
      (node (ref "C15") (pin "2") (pinfunction "2_2") (pintype "passive"))
      (node (ref "C16") (pin "2") (pinfunction "2_2") (pintype "passive"))
      (node (ref "C17") (pin "2") (pinfunction "2_2") (pintype "passive"))
      (node (ref "C18") (pin "1") (pinfunction "1_1") (pintype "passive"))
      (node (ref "C19") (pin "1") (pinfunction "1_1") (pintype "passive"))
      (node (ref "C20") (pin "2") (pinfunction "2_2") (pintype "passive"))
      (node (ref "C21") (pin "2") (pinfunction "2_2") (pintype "passive"))
      (node (ref "C22") (pin "2") (pinfunction "2_2") (pintype "passive"))
      (node (ref "C23") (pin "2") (pinfunction "2_2") (pintype "passive"))
      (node (ref "C24") (pin "2") (pinfunction "2_2") (pintype "passive"))
      (node (ref "C25") (pin "2") (pinfunction "2_2") (pintype "passive"))
      (node (ref "C26") (pin "1") (pinfunction "1_1") (pintype "passive"))
      (node (ref "C27") (pin "2") (pinfunction "2_2") (pintype "passive"))
      (node (ref "C28") (pin "1") (pinfunction "1_1") (pintype "passive"))
      (node (ref "C29") (pin "2") (pinfunction "2_2") (pintype "passive"))
      (node (ref "C30") (pin "2") (pinfunction "2_2") (pintype "passive"))
      (node (ref "C31") (pin "1") (pinfunction "1_1") (pintype "passive"))
      (node (ref "C32") (pin "1") (pinfunction "1_1") (pintype "passive"))
      (node (ref "C33") (pin "1") (pinfunction "1_1") (pintype "passive"))
      (node (ref "C34") (pin "2") (pinfunction "2_2") (pintype "passive"))
      (node (ref "C35") (pin "1") (pinfunction "1_1") (pintype "passive"))
      (node (ref "C36") (pin "1") (pinfunction "1_1") (pintype "passive"))
      (node (ref "C37") (pin "1") (pinfunction "1_1") (pintype "passive"))
      (node (ref "C8") (pin "2") (pinfunction "2_2") (pintype "passive"))
      (node (ref "C9") (pin "2") (pinfunction "2_2") (pintype "passive"))
      (node (ref "D4") (pin "A") (pinfunction "1_A") (pintype "passive"))
      (node (ref "P11") (pin "2") (pinfunction "2_2") (pintype "passive"))
      (node (ref "P12") (pin "4") (pinfunction "4_4") (pintype "input"))
      (node (ref "P13") (pin "1") (pinfunction "1_1") (pintype "passive"))
      (node (ref "P2") (pin "2") (pinfunction "2_2") (pintype "passive"))
      (node (ref "P2") (pin "7") (pinfunction "7_7") (pintype "passive"))
      (node (ref "P3") (pin "1") (pinfunction "1_1") (pintype "passive"))
      (node (ref "P4") (pin "2") (pinfunction "2_2") (pintype "passive"))
      (node (ref "P5") (pin "2") (pinfunction "2_2") (pintype "passive"))
      (node (ref "P6") (pin "1") (pinfunction "GND_1") (pintype "power_in"))
      (node (ref "P7") (pin "4") (pinfunction "4_4") (pintype "passive"))
      (node (ref "P8") (pin "1") (pinfunction "1_1") (pintype "passive"))
      (node (ref "Q1") (pin "E") (pinfunction "e_E") (pintype "passive"))
      (node (ref "R10") (pin "1") (pinfunction "1_1") (pintype "passive"))
      (node (ref "R14") (pin "1") (pinfunction "1_1") (pintype "passive"))
      (node (ref "R18") (pin "2") (pinfunction "2_2") (pintype "passive"))
      (node (ref "R6") (pin "2") (pinfunction "2_2") (pintype "passive"))
      (node (ref "R8") (pin "2") (pinfunction "2_2") (pintype "passive"))
      (node (ref "S2") (pin "2") (pinfunction "NC1_2") (pintype "passive"))
      (node (ref "U19") (pin "1") (pinfunction "GND_1") (pintype "power_in"))
      (node (ref "U3") (pin "23") (pinfunction "VSS_1_23") (pintype "power_in"))
      (node (ref "U3") (pin "35") (pinfunction "VSS_2_35") (pintype "power_in"))
      (node (ref "U3") (pin "47") (pinfunction "VSS_3_47") (pintype "power_in"))
      (node (ref "U3") (pin "8") (pinfunction "VSSA_8") (pintype "power_in"))
      (node (ref "U4") (pin "2") (pinfunction "GND_2") (pintype "power_in"))
      (node (ref "U6") (pin "1") (pinfunction "GND_1") (pintype "passive"))
      (node (ref "U7") (pin "1") (pinfunction "CLKIN_1") (pintype "input"))
      (node (ref "U7") (pin "11") (pinfunction "FSYNC_11") (pintype "bidirectional"))
      (node (ref "U7") (pin "18") (pinfunction "gnd_18") (pintype "power_in"))
      (node (ref "U8") (pin "1") (pinfunction "GND_1") (pintype "passive"))
      (node (ref "key1") (pin "2") (pinfunction "2_2") (pintype "passive"))
    )
    (net (code "45") (name "Net-(D4-2)") (class "Default")
      (node (ref "C7") (pin "2") (pinfunction "2_2") (pintype "passive"))
      (node (ref "D4") (pin "K") (pinfunction "2_K") (pintype "passive"))
      (node (ref "L2") (pin "1") (pinfunction "1_1") (pintype "passive"))
      (node (ref "U4") (pin "6") (pinfunction "SW_6") (pintype "input"))
    )
    (net (code "46") (name "Net-(D5-1)") (class "Default")
      (node (ref "D5") (pin "K1") (pinfunction "1_K1") (pintype "passive"))
      (node (ref "R14") (pin "2") (pinfunction "2_2") (pintype "passive"))
    )
    (net (code "47") (name "Net-(D5-3)") (class "Default")
      (node (ref "D5") (pin "K2") (pinfunction "3_K2") (pintype "passive"))
      (node (ref "R15") (pin "2") (pinfunction "2_2") (pintype "passive"))
    )
    (net (code "48") (name "Net-(D6-1)") (class "Default")
      (node (ref "D6") (pin "K1") (pinfunction "1_K1") (pintype "passive"))
      (node (ref "R16") (pin "2") (pinfunction "2_2") (pintype "passive"))
    )
    (net (code "49") (name "Net-(D6-3)") (class "Default")
      (node (ref "D6") (pin "K2") (pinfunction "3_K2") (pintype "passive"))
      (node (ref "R17") (pin "2") (pinfunction "2_2") (pintype "passive"))
    )
    (net (code "50") (name "Net-(P13-Pad3)") (class "Default")
      (node (ref "P13") (pin "3") (pinfunction "3_3") (pintype "passive"))
      (node (ref "R28") (pin "2") (pinfunction "2_2") (pintype "passive"))
      (node (ref "R29") (pin "2") (pinfunction "2_2") (pintype "passive"))
    )
    (net (code "51") (name "Net-(Q1-b)") (class "Default")
      (node (ref "Q1") (pin "B") (pinfunction "b_B") (pintype "passive"))
      (node (ref "R1") (pin "1") (pinfunction "1_1") (pintype "passive"))
    )
    (net (code "52") (name "Net-(Q1-c)") (class "Default")
      (node (ref "Q1") (pin "C") (pinfunction "c_C") (pintype "passive"))
      (node (ref "U5") (pin "2") (pinfunction "B_2") (pintype "passive"))
    )
    (net (code "53") (name "Net-(S2-COMMON1)") (class "Default")
      (node (ref "R12") (pin "2") (pinfunction "2_2") (pintype "passive"))
      (node (ref "S2") (pin "1") (pinfunction "COMMON1_1") (pintype "passive"))
    )
    (net (code "54") (name "Net-(U3-BOOT0)") (class "Default")
      (node (ref "R10") (pin "2") (pinfunction "2_2") (pintype "passive"))
      (node (ref "U3") (pin "44") (pinfunction "BOOT0_44") (pintype "input"))
    )
    (net (code "55") (name "Net-(U3-NRST)") (class "Default")
      (node (ref "C22") (pin "1") (pinfunction "1_1") (pintype "passive"))
      (node (ref "R11") (pin "2") (pinfunction "2_2") (pintype "passive"))
      (node (ref "U3") (pin "7") (pinfunction "NRST_7") (pintype "bidirectional"))
      (node (ref "key1") (pin "1") (pinfunction "1_1") (pintype "passive"))
    )
    (net (code "56") (name "Net-(U3-OSC_IN{slash}PD0)") (class "Default")
      (node (ref "C18") (pin "2") (pinfunction "2_2") (pintype "passive"))
      (node (ref "U3") (pin "5") (pinfunction "OSC_IN/PD0_5") (pintype "input"))
      (node (ref "Y1") (pin "2") (pinfunction "OSC2_2") (pintype "passive"))
    )
    (net (code "57") (name "Net-(U3-OSC_OUT{slash}PD1)") (class "Default")
      (node (ref "C19") (pin "2") (pinfunction "2_2") (pintype "passive"))
      (node (ref "U3") (pin "6") (pinfunction "OSC_OUT/PD1_6") (pintype "output"))
      (node (ref "Y1") (pin "1") (pinfunction "OSC1_1") (pintype "passive"))
    )
    (net (code "58") (name "Net-(U4-BST)") (class "Default")
      (node (ref "C7") (pin "1") (pinfunction "1_1") (pintype "passive"))
      (node (ref "U4") (pin "1") (pinfunction "BST_1") (pintype "output"))
    )
    (net (code "59") (name "Net-(U4-FB)") (class "Default")
      (node (ref "R8") (pin "1") (pinfunction "1_1") (pintype "passive"))
      (node (ref "R9") (pin "2") (pinfunction "2_2") (pintype "passive"))
      (node (ref "U4") (pin "3") (pinfunction "FB_3") (pintype "output"))
    )
    (net (code "60") (name "Net-(U7-ADO)") (class "Default")
      (node (ref "R18") (pin "1") (pinfunction "1_1") (pintype "passive"))
      (node (ref "U7") (pin "9") (pinfunction "ADO_9") (pintype "output"))
    )
    (net (code "61") (name "Net-(U7-CPOUT)") (class "Default")
      (node (ref "C36") (pin "2") (pinfunction "2_2") (pintype "passive"))
      (node (ref "U7") (pin "20") (pinfunction "CPOUT_20") (pintype "output"))
    )
    (net (code "62") (name "Net-(U7-REGOUT)") (class "Default")
      (node (ref "C37") (pin "2") (pinfunction "2_2") (pintype "passive"))
      (node (ref "U7") (pin "10") (pinfunction "REGOUT_10") (pintype "output"))
    )
    (net (code "63") (name "Net-(U8-V3)") (class "Default")
      (node (ref "C31") (pin "2") (pinfunction "2_2") (pintype "passive"))
      (node (ref "U8") (pin "4") (pinfunction "V3_4") (pintype "passive"))
    )
    (net (code "64") (name "Net-(U8-XI)") (class "Default")
      (node (ref "C32") (pin "2") (pinfunction "2_2") (pintype "passive"))
      (node (ref "U8") (pin "7") (pinfunction "XI_7") (pintype "passive"))
      (node (ref "Y2") (pin "2") (pinfunction "OSC2_2") (pintype "passive"))
    )
    (net (code "65") (name "Net-(U8-XO)") (class "Default")
      (node (ref "C33") (pin "2") (pinfunction "2_2") (pintype "passive"))
      (node (ref "U8") (pin "8") (pinfunction "XO_8") (pintype "passive"))
      (node (ref "Y2") (pin "1") (pinfunction "OSC1_1") (pintype "passive"))
    )
    (net (code "66") (name "VCC_BAT") (class "Default")
      (node (ref "P11") (pin "1") (pinfunction "1_1") (pintype "passive"))
      (node (ref "S1") (pin "1") (pinfunction "COMMON1_1") (pintype "passive"))
    )
    (net (code "67") (name "Vin9V") (class "Default")
      (node (ref "C12") (pin "1") (pinfunction "1_1") (pintype "passive"))
      (node (ref "D3") (pin "K") (pinfunction "2_K") (pintype "passive"))
      (node (ref "R5") (pin "1") (pinfunction "1_1") (pintype "passive"))
      (node (ref "R7") (pin "2") (pinfunction "2_2") (pintype "passive"))
      (node (ref "U4") (pin "5") (pinfunction "IN_5") (pintype "power_in"))
    )
    (net (code "68") (name "VinM9V") (class "Default")
      (node (ref "D3") (pin "A") (pinfunction "1_A") (pintype "passive"))
      (node (ref "P13") (pin "2") (pinfunction "2_2") (pintype "passive"))
      (node (ref "S1") (pin "2") (pinfunction "NC1_2") (pintype "power_in"))
    )
    (net (code "69") (name "unconnected-(P5-Pad7)") (class "Default")
      (node (ref "P5") (pin "7") (pinfunction "7_7") (pintype "passive"))
    )
    (net (code "70") (name "unconnected-(P6-ID-Pad2)") (class "Default")
      (node (ref "P6") (pin "2") (pinfunction "ID_2") (pintype "passive"))
    )
    (net (code "71") (name "unconnected-(U3-PB4{slash}JNTRST-Pad40)") (class "Default")
      (node (ref "U3") (pin "40") (pinfunction "PB4/JNTRST_40") (pintype "bidirectional"))
    )
    (net (code "72") (name "unconnected-(U7-auxcl-Pad7)") (class "Default")
      (node (ref "U7") (pin "7") (pinfunction "auxcl_7") (pintype "bidirectional"))
    )
    (net (code "73") (name "unconnected-(U7-auxda-Pad6)") (class "Default")
      (node (ref "U7") (pin "6") (pinfunction "auxda_6") (pintype "bidirectional"))
    )
    (net (code "74") (name "unconnected-(U7-clkout-Pad22)") (class "Default")
      (node (ref "U7") (pin "22") (pinfunction "clkout_22") (pintype "output+no_connect"))
    )
    (net (code "75") (name "unconnected-(U7-resv-Pad19)") (class "Default")
      (node (ref "U7") (pin "19") (pinfunction "resv_19") (pintype "input+no_connect"))
    )
    (net (code "76") (name "unconnected-(U7-resv-Pad21)") (class "Default")
      (node (ref "U7") (pin "21") (pinfunction "resv_21") (pintype "input+no_connect"))
    )
    (net (code "77") (name "unconnected-(U8-CTS#-Pad9)") (class "Default")
      (node (ref "U8") (pin "9") (pinfunction "CTS#_9") (pintype "passive"))
    )
    (net (code "78") (name "unconnected-(U8-DCD#-Pad12)") (class "Default")
      (node (ref "U8") (pin "12") (pinfunction "DCD#_12") (pintype "passive"))
    )
    (net (code "79") (name "unconnected-(U8-DSR#-Pad10)") (class "Default")
      (node (ref "U8") (pin "10") (pinfunction "DSR#_10") (pintype "passive"))
    )
    (net (code "80") (name "unconnected-(U8-DTR#-Pad13)") (class "Default")
      (node (ref "U8") (pin "13") (pinfunction "DTR#_13") (pintype "passive"))
    )
    (net (code "81") (name "unconnected-(U8-R232-Pad15)") (class "Default")
      (node (ref "U8") (pin "15") (pinfunction "R232_15") (pintype "passive"))
    )
    (net (code "82") (name "unconnected-(U8-RI#-Pad11)") (class "Default")
      (node (ref "U8") (pin "11") (pinfunction "RI#_11") (pintype "passive"))
    )
    (net (code "83") (name "unconnected-(U8-RTS#-Pad14)") (class "Default")
      (node (ref "U8") (pin "14") (pinfunction "RTS#_14") (pintype "passive"))
    )
  )
)
